# Amiga_Parallel_SD_Rev_2.net
KiCad netlist of a schematic drawn in EAGLE
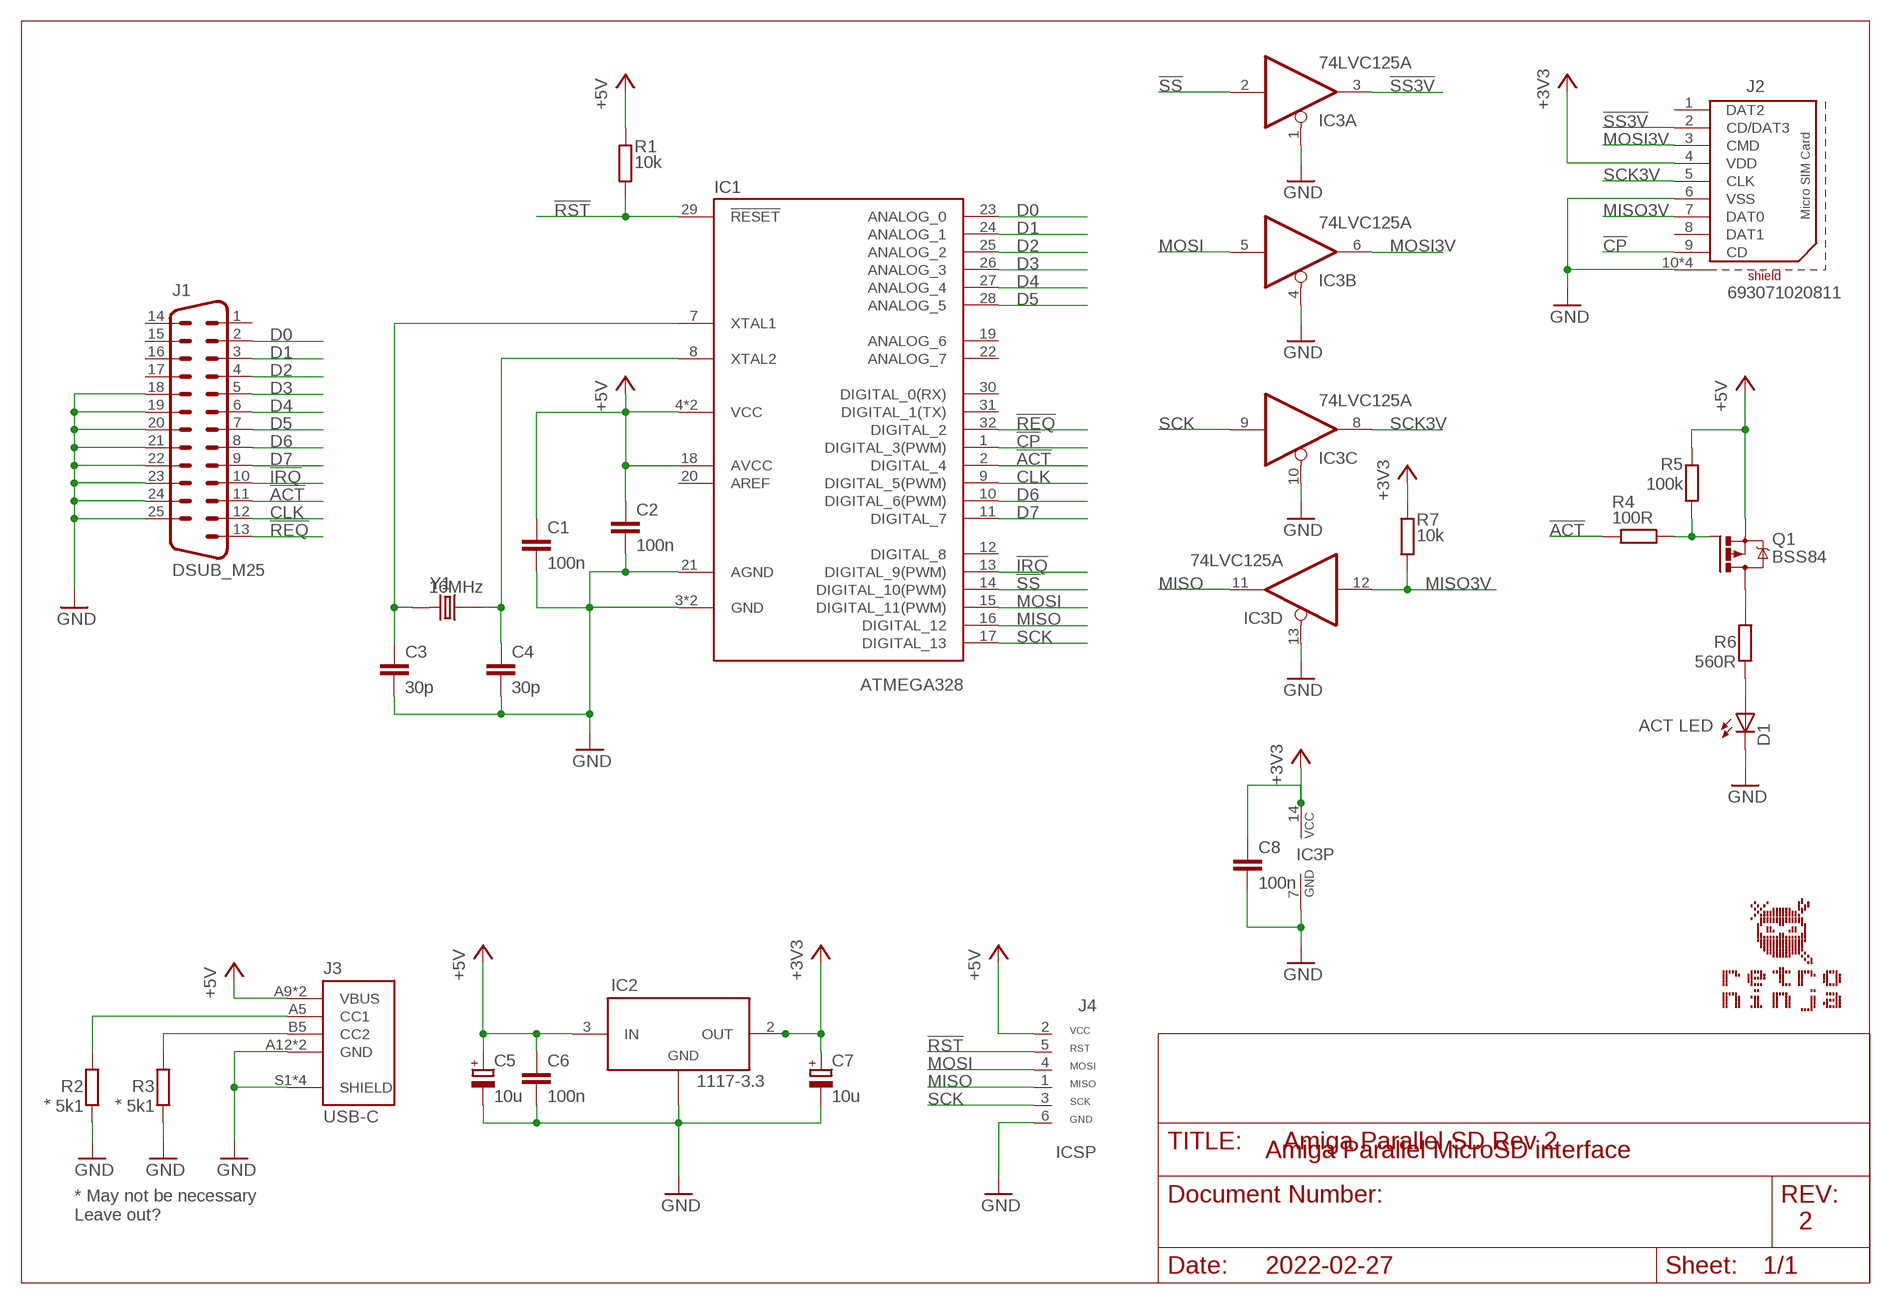
[diagram p0: schematic, sheet 1]

(export (version "E")
  (design (tool "Eeschema 10.0.6"))
  (components
    (comp (ref "C1")
      (value "100n")
      (footprint "eagle-import:C0805")
      (libsource (lib "eagle-import") (part "C-EUC0805"))
    )
    (comp (ref "C2")
      (value "100n")
      (footprint "eagle-import:C0805")
      (libsource (lib "eagle-import") (part "C-EUC0805"))
    )
    (comp (ref "C3")
      (value "30p")
      (footprint "eagle-import:C0805")
      (libsource (lib "eagle-import") (part "C-EUC0805"))
    )
    (comp (ref "C4")
      (value "30p")
      (footprint "eagle-import:C0805")
      (libsource (lib "eagle-import") (part "C-EUC0805"))
    )
    (comp (ref "C5")
      (value "10u")
      (footprint "eagle-import:TANTALUM_0805")
      (libsource (lib "eagle-import") (part "CAPACITOR_POL_TANT_0805"))
    )
    (comp (ref "C6")
      (value "100n")
      (footprint "eagle-import:C0805")
      (libsource (lib "eagle-import") (part "C-EUC0805"))
    )
    (comp (ref "C7")
      (value "10u")
      (footprint "eagle-import:TANTALUM_0805")
      (libsource (lib "eagle-import") (part "CAPACITOR_POL_TANT_0805"))
    )
    (comp (ref "C8")
      (value "100n")
      (footprint "eagle-import:C0805")
      (libsource (lib "eagle-import") (part "C-EUC0805"))
    )
    (comp (ref "D1")
      (value "LED_3MM_GREEN")
      (footprint "eagle-import:LED3MM_GREEN")
      (libsource (lib "eagle-import") (part "LED_3MM_GREEN"))
    )
    (comp (ref "IC1")
      (value "ATMEGA328")
      (footprint "eagle-import:TQFP-32")
      (libsource (lib "eagle-import") (part "ARDUINO_168_328_TQFP"))
    )
    (comp (ref "IC2")
      (value "1117-3.3")
      (footprint "eagle-import:SOT-223")
      (fields
        (field (name "DIGIKEY_PART_NUMBER") "NCP1117ST33T3GOSTR-ND")
        (field (name "MANUFACTURER") "ON Semiconductor")
        (field (name "MPN") "NCP1117ST33T3G")
        (field (name "CREATED_BY") "PCBLayout.com")
      )
      (libsource (lib "eagle-import") (part "NCP1117ST33T3G"))
    )
    (comp (ref "IC3")
      (value "74LVC125A")
      (footprint "eagle-import:SO14")
      (libsource (lib "eagle-import") (part "74125DHC"))
    )
    (comp (ref "J1")
      (value "DSUB_M25")
      (footprint "eagle-import:DSUB_M25D")
      (libsource (lib "eagle-import") (part "DSUB_M25"))
    )
    (comp (ref "J2")
      (value "693071020811")
      (footprint "eagle-import:693071020811")
      (libsource (lib "eagle-import") (part "693071020811"))
    )
    (comp (ref "J3")
      (value "USB-C")
      (footprint "eagle-import:MOLEX_2171750001")
      (fields (field (name "MANUFACTURER") "Molex"))
      (libsource (lib "eagle-import") (part "USB-C"))
    )
    (comp (ref "J4")
      (value "ICSP")
      (footprint "eagle-import:HEADER_2X3_ALT")
      (libsource (lib "eagle-import") (part "ICSP_CONNECTOR_6_ALT"))
    )
    (comp (ref "Q1")
      (value "BSS84")
      (footprint "eagle-import:SOT23")
      (libsource (lib "eagle-import") (part "PMOSFETSOT23_"))
    )
    (comp (ref "R1")
      (value "10k")
      (footprint "eagle-import:R0805")
      (libsource (lib "eagle-import") (part "R-EU_R0805"))
    )
    (comp (ref "R2")
      (value "5k1")
      (footprint "eagle-import:R0805")
      (libsource (lib "eagle-import") (part "R-EU_R0805"))
    )
    (comp (ref "R3")
      (value "5k1")
      (footprint "eagle-import:R0805")
      (libsource (lib "eagle-import") (part "R-EU_R0805"))
    )
    (comp (ref "R4")
      (value "100R")
      (footprint "eagle-import:R0805")
      (libsource (lib "eagle-import") (part "R-EU_R0805"))
    )
    (comp (ref "R5")
      (value "100k")
      (footprint "eagle-import:R0805")
      (libsource (lib "eagle-import") (part "R-EU_R0805"))
    )
    (comp (ref "R6")
      (value "560R")
      (footprint "eagle-import:R0805")
      (libsource (lib "eagle-import") (part "R-EU_R0805"))
    )
    (comp (ref "R7")
      (value "10k")
      (footprint "eagle-import:R0805")
      (libsource (lib "eagle-import") (part "R-EU_R0805"))
    )
    (comp (ref "Y1")
      (value "16MHz")
      (footprint "eagle-import:CRYSTAL_SMD-2_7X4X2.3")
      (libsource (lib "eagle-import") (part "CRYSTAL"))
    )
  )
  (nets
    (net (code "1") (name "+3V3") (class "Default")
      (node (ref "C7") (pin "+") (pinfunction "+_+") (pintype "passive"))
      (node (ref "C8") (pin "1") (pinfunction "1_1") (pintype "passive"))
      (node (ref "IC2") (pin "2") (pinfunction "OUT_2") (pintype "output"))
      (node (ref "IC2") (pin "4") (pinfunction "4_4") (pintype "passive"))
      (node (ref "IC3") (pin "14") (pinfunction "VCC_14") (pintype "power_in"))
      (node (ref "J2") (pin "4") (pinfunction "VDD_4") (pintype "bidirectional"))
      (node (ref "R7") (pin "1") (pinfunction "1_1") (pintype "passive"))
    )
    (net (code "2") (name "+5V") (class "Default")
      (node (ref "C1") (pin "1") (pinfunction "1_1") (pintype "passive"))
      (node (ref "C2") (pin "1") (pinfunction "1_1") (pintype "passive"))
      (node (ref "C5") (pin "+") (pinfunction "+_+") (pintype "passive"))
      (node (ref "C6") (pin "1") (pinfunction "1_1") (pintype "passive"))
      (node (ref "IC1") (pin "18") (pinfunction "AVCC_18") (pintype "passive"))
      (node (ref "IC1") (pin "4") (pinfunction "VCC_4") (pintype "passive"))
      (node (ref "IC1") (pin "6") (pinfunction "VCC_6") (pintype "passive"))
      (node (ref "IC2") (pin "3") (pinfunction "IN_3") (pintype "input"))
      (node (ref "J3") (pin "A9") (pinfunction "VBUS_A9") (pintype "power_in"))
      (node (ref "J3") (pin "B9") (pinfunction "VBUS_B9") (pintype "power_in"))
      (node (ref "J4") (pin "2") (pinfunction "VCC_2") (pintype "power_in"))
      (node (ref "Q1") (pin "2") (pinfunction "S_2") (pintype "passive"))
      (node (ref "R1") (pin "1") (pinfunction "1_1") (pintype "passive"))
      (node (ref "R5") (pin "2") (pinfunction "2_2") (pintype "passive"))
    )
    (net (code "3") (name "/CLK") (class "Default")
      (node (ref "IC1") (pin "9") (pinfunction "DIGITAL_5(PWM)_9") (pintype "bidirectional"))
      (node (ref "J1") (pin "12") (pinfunction "12_12") (pintype "passive"))
    )
    (net (code "4") (name "/D0") (class "Default")
      (node (ref "IC1") (pin "23") (pinfunction "ANALOG_0_23") (pintype "bidirectional"))
      (node (ref "J1") (pin "2") (pinfunction "2_2") (pintype "passive"))
    )
    (net (code "5") (name "/D1") (class "Default")
      (node (ref "IC1") (pin "24") (pinfunction "ANALOG_1_24") (pintype "bidirectional"))
      (node (ref "J1") (pin "3") (pinfunction "3_3") (pintype "passive"))
    )
    (net (code "6") (name "/D2") (class "Default")
      (node (ref "IC1") (pin "25") (pinfunction "ANALOG_2_25") (pintype "bidirectional"))
      (node (ref "J1") (pin "4") (pinfunction "4_4") (pintype "passive"))
    )
    (net (code "7") (name "/D3") (class "Default")
      (node (ref "IC1") (pin "26") (pinfunction "ANALOG_3_26") (pintype "bidirectional"))
      (node (ref "J1") (pin "5") (pinfunction "5_5") (pintype "passive"))
    )
    (net (code "8") (name "/D4") (class "Default")
      (node (ref "IC1") (pin "27") (pinfunction "ANALOG_4_27") (pintype "bidirectional"))
      (node (ref "J1") (pin "6") (pinfunction "6_6") (pintype "passive"))
    )
    (net (code "9") (name "/D5") (class "Default")
      (node (ref "IC1") (pin "28") (pinfunction "ANALOG_5_28") (pintype "bidirectional"))
      (node (ref "J1") (pin "7") (pinfunction "7_7") (pintype "passive"))
    )
    (net (code "10") (name "/D6") (class "Default")
      (node (ref "IC1") (pin "10") (pinfunction "DIGITAL_6(PWM)_10") (pintype "bidirectional"))
      (node (ref "J1") (pin "8") (pinfunction "8_8") (pintype "passive"))
    )
    (net (code "11") (name "/D7") (class "Default")
      (node (ref "IC1") (pin "11") (pinfunction "DIGITAL_7_11") (pintype "bidirectional"))
      (node (ref "J1") (pin "9") (pinfunction "9_9") (pintype "passive"))
    )
    (net (code "12") (name "/MISO") (class "Default")
      (node (ref "IC1") (pin "16") (pinfunction "DIGITAL_12_16") (pintype "bidirectional"))
      (node (ref "IC3") (pin "11") (pinfunction "O_11") (pintype "tri_state"))
      (node (ref "J4") (pin "1") (pinfunction "MISO_1") (pintype "output"))
    )
    (net (code "13") (name "/MISO3V") (class "Default")
      (node (ref "IC3") (pin "12") (pinfunction "I_12") (pintype "input"))
      (node (ref "J2") (pin "7") (pinfunction "DAT0_7") (pintype "bidirectional"))
      (node (ref "R7") (pin "2") (pinfunction "2_2") (pintype "passive"))
    )
    (net (code "14") (name "/MOSI") (class "Default")
      (node (ref "IC1") (pin "15") (pinfunction "DIGITAL_11(PWM)_15") (pintype "bidirectional"))
      (node (ref "IC3") (pin "5") (pinfunction "I_5") (pintype "input"))
      (node (ref "J4") (pin "4") (pinfunction "MOSI_4") (pintype "input"))
    )
    (net (code "15") (name "/MOSI3V") (class "Default")
      (node (ref "IC3") (pin "6") (pinfunction "O_6") (pintype "tri_state"))
      (node (ref "J2") (pin "3") (pinfunction "CMD_3") (pintype "bidirectional"))
    )
    (net (code "16") (name "/SCK") (class "Default")
      (node (ref "IC1") (pin "17") (pinfunction "DIGITAL_13_17") (pintype "bidirectional"))
      (node (ref "IC3") (pin "9") (pinfunction "I_9") (pintype "input"))
      (node (ref "J4") (pin "3") (pinfunction "SCK_3") (pintype "input"))
    )
    (net (code "17") (name "/SCK3V") (class "Default")
      (node (ref "IC3") (pin "8") (pinfunction "O_8") (pintype "tri_state"))
      (node (ref "J2") (pin "5") (pinfunction "CLK_5") (pintype "bidirectional"))
    )
    (net (code "18") (name "/~{ACT}") (class "Default")
      (node (ref "IC1") (pin "2") (pinfunction "DIGITAL_4_2") (pintype "bidirectional"))
      (node (ref "J1") (pin "11") (pinfunction "11_11") (pintype "passive"))
      (node (ref "R4") (pin "2") (pinfunction "2_2") (pintype "passive"))
    )
    (net (code "19") (name "/~{CP}") (class "Default")
      (node (ref "IC1") (pin "1") (pinfunction "DIGITAL_3(PWM)_1") (pintype "bidirectional"))
      (node (ref "J2") (pin "9") (pinfunction "CD_9") (pintype "bidirectional"))
    )
    (net (code "20") (name "/~{IRQ}") (class "Default")
      (node (ref "IC1") (pin "13") (pinfunction "DIGITAL_9(PWM)_13") (pintype "bidirectional"))
      (node (ref "J1") (pin "10") (pinfunction "10_10") (pintype "passive"))
    )
    (net (code "21") (name "/~{REQ}") (class "Default")
      (node (ref "IC1") (pin "32") (pinfunction "DIGITAL_2_32") (pintype "bidirectional"))
      (node (ref "J1") (pin "13") (pinfunction "13_13") (pintype "passive"))
    )
    (net (code "22") (name "/~{RST}") (class "Default")
      (node (ref "IC1") (pin "29") (pinfunction "~{RESET}_29") (pintype "bidirectional"))
      (node (ref "J4") (pin "5") (pinfunction "RST_5") (pintype "input"))
      (node (ref "R1") (pin "2") (pinfunction "2_2") (pintype "passive"))
    )
    (net (code "23") (name "/~{SS3V}") (class "Default")
      (node (ref "IC3") (pin "3") (pinfunction "O_3") (pintype "tri_state"))
      (node (ref "J2") (pin "2") (pinfunction "CD/DAT3_2") (pintype "bidirectional"))
    )
    (net (code "24") (name "/~{SS}") (class "Default")
      (node (ref "IC1") (pin "14") (pinfunction "DIGITAL_10(PWM)_14") (pintype "bidirectional"))
      (node (ref "IC3") (pin "2") (pinfunction "I_2") (pintype "input"))
    )
    (net (code "25") (name "GND") (class "Default")
      (node (ref "C1") (pin "2") (pinfunction "2_2") (pintype "passive"))
      (node (ref "C2") (pin "2") (pinfunction "2_2") (pintype "passive"))
      (node (ref "C3") (pin "2") (pinfunction "2_2") (pintype "passive"))
      (node (ref "C4") (pin "2") (pinfunction "2_2") (pintype "passive"))
      (node (ref "C5") (pin "-") (pinfunction "-_-") (pintype "passive"))
      (node (ref "C6") (pin "2") (pinfunction "2_2") (pintype "passive"))
      (node (ref "C7") (pin "-") (pinfunction "-_-") (pintype "passive"))
      (node (ref "C8") (pin "2") (pinfunction "2_2") (pintype "passive"))
      (node (ref "D1") (pin "K") (pinfunction "C_K") (pintype "passive"))
      (node (ref "IC1") (pin "21") (pinfunction "AGND_21") (pintype "passive"))
      (node (ref "IC1") (pin "3") (pinfunction "GND_3") (pintype "passive"))
      (node (ref "IC1") (pin "5") (pinfunction "GND_5") (pintype "passive"))
      (node (ref "IC2") (pin "1") (pinfunction "ADJ/GND_1") (pintype "power_in"))
      (node (ref "IC3") (pin "1") (pinfunction "OE_1") (pintype "input"))
      (node (ref "IC3") (pin "10") (pinfunction "OE_10") (pintype "input"))
      (node (ref "IC3") (pin "13") (pinfunction "OE_13") (pintype "input"))
      (node (ref "IC3") (pin "4") (pinfunction "OE_4") (pintype "input"))
      (node (ref "IC3") (pin "7") (pinfunction "GND_7") (pintype "power_in"))
      (node (ref "J1") (pin "18") (pinfunction "18_18") (pintype "passive"))
      (node (ref "J1") (pin "19") (pinfunction "19_19") (pintype "passive"))
      (node (ref "J1") (pin "20") (pinfunction "20_20") (pintype "passive"))
      (node (ref "J1") (pin "21") (pinfunction "21_21") (pintype "passive"))
      (node (ref "J1") (pin "22") (pinfunction "22_22") (pintype "passive"))
      (node (ref "J1") (pin "23") (pinfunction "23_23") (pintype "passive"))
      (node (ref "J1") (pin "24") (pinfunction "24_24") (pintype "passive"))
      (node (ref "J1") (pin "25") (pinfunction "25_25") (pintype "passive"))
      (node (ref "J2") (pin "10") (pinfunction "SHIELD_10") (pintype "bidirectional"))
      (node (ref "J2") (pin "11") (pinfunction "SHIELD_11") (pintype "bidirectional"))
      (node (ref "J2") (pin "12") (pinfunction "SHIELD_12") (pintype "bidirectional"))
      (node (ref "J2") (pin "13") (pinfunction "SHIELD_13") (pintype "bidirectional"))
      (node (ref "J2") (pin "6") (pinfunction "VSS_6") (pintype "bidirectional"))
      (node (ref "J3") (pin "A12") (pinfunction "GND_A12") (pintype "power_in"))
      (node (ref "J3") (pin "B12") (pinfunction "GND_B12") (pintype "power_in"))
      (node (ref "J3") (pin "S1") (pinfunction "SHIELD_S1") (pintype "passive"))
      (node (ref "J3") (pin "S2") (pinfunction "SHIELD_S2") (pintype "passive"))
      (node (ref "J3") (pin "S3") (pinfunction "SHIELD_S3") (pintype "passive"))
      (node (ref "J3") (pin "S4") (pinfunction "SHIELD_S4") (pintype "passive"))
      (node (ref "J4") (pin "6") (pinfunction "GND_6") (pintype "power_in"))
      (node (ref "R2") (pin "1") (pinfunction "1_1") (pintype "passive"))
      (node (ref "R3") (pin "1") (pinfunction "1_1") (pintype "passive"))
    )
    (net (code "26") (name "Net-(D1-PadA)") (class "Default")
      (node (ref "D1") (pin "A") (pinfunction "A_A") (pintype "passive"))
      (node (ref "R6") (pin "1") (pinfunction "1_1") (pintype "passive"))
    )
    (net (code "27") (name "Net-(IC1-XTAL1)") (class "Default")
      (node (ref "C3") (pin "1") (pinfunction "1_1") (pintype "passive"))
      (node (ref "IC1") (pin "7") (pinfunction "XTAL1_7") (pintype "bidirectional"))
      (node (ref "Y1") (pin "2") (pinfunction "2_2") (pintype "passive"))
    )
    (net (code "28") (name "Net-(IC1-XTAL2)") (class "Default")
      (node (ref "C4") (pin "1") (pinfunction "1_1") (pintype "passive"))
      (node (ref "IC1") (pin "8") (pinfunction "XTAL2_8") (pintype "bidirectional"))
      (node (ref "Y1") (pin "1") (pinfunction "1_1") (pintype "passive"))
    )
    (net (code "29") (name "Net-(J3-CC1)") (class "Default")
      (node (ref "J3") (pin "A5") (pinfunction "CC1_A5") (pintype "bidirectional"))
      (node (ref "R2") (pin "2") (pinfunction "2_2") (pintype "passive"))
    )
    (net (code "30") (name "Net-(J3-CC2)") (class "Default")
      (node (ref "J3") (pin "B5") (pinfunction "CC2_B5") (pintype "bidirectional"))
      (node (ref "R3") (pin "2") (pinfunction "2_2") (pintype "passive"))
    )
    (net (code "31") (name "Net-(Q1-D)") (class "Default")
      (node (ref "Q1") (pin "3") (pinfunction "D_3") (pintype "passive"))
      (node (ref "R6") (pin "2") (pinfunction "2_2") (pintype "passive"))
    )
    (net (code "32") (name "Net-(Q1-G)") (class "Default")
      (node (ref "Q1") (pin "1") (pinfunction "G_1") (pintype "passive"))
      (node (ref "R4") (pin "1") (pinfunction "1_1") (pintype "passive"))
      (node (ref "R5") (pin "1") (pinfunction "1_1") (pintype "passive"))
    )
    (net (code "33") (name "unconnected-(IC1-ANALOG_6-Pad19)") (class "Default")
      (node (ref "IC1") (pin "19") (pinfunction "ANALOG_6_19") (pintype "bidirectional"))
    )
    (net (code "34") (name "unconnected-(IC1-ANALOG_7-Pad22)") (class "Default")
      (node (ref "IC1") (pin "22") (pinfunction "ANALOG_7_22") (pintype "bidirectional"))
    )
    (net (code "35") (name "unconnected-(IC1-AREF-Pad20)") (class "Default")
      (node (ref "IC1") (pin "20") (pinfunction "AREF_20") (pintype "passive"))
    )
    (net (code "36") (name "unconnected-(IC1-DIGITAL_0(RX)-Pad30)") (class "Default")
      (node (ref "IC1") (pin "30") (pinfunction "DIGITAL_0(RX)_30") (pintype "bidirectional"))
    )
    (net (code "37") (name "unconnected-(IC1-DIGITAL_1(TX)-Pad31)") (class "Default")
      (node (ref "IC1") (pin "31") (pinfunction "DIGITAL_1(TX)_31") (pintype "bidirectional"))
    )
    (net (code "38") (name "unconnected-(IC1-DIGITAL_8-Pad12)") (class "Default")
      (node (ref "IC1") (pin "12") (pinfunction "DIGITAL_8_12") (pintype "bidirectional"))
    )
    (net (code "39") (name "unconnected-(J1-Pad1)") (class "Default")
      (node (ref "J1") (pin "1") (pinfunction "1_1") (pintype "passive"))
    )
    (net (code "40") (name "unconnected-(J1-Pad14)") (class "Default")
      (node (ref "J1") (pin "14") (pinfunction "14_14") (pintype "passive"))
    )
    (net (code "41") (name "unconnected-(J1-Pad15)") (class "Default")
      (node (ref "J1") (pin "15") (pinfunction "15_15") (pintype "passive"))
    )
    (net (code "42") (name "unconnected-(J1-Pad16)") (class "Default")
      (node (ref "J1") (pin "16") (pinfunction "16_16") (pintype "passive"))
    )
    (net (code "43") (name "unconnected-(J1-Pad17)") (class "Default")
      (node (ref "J1") (pin "17") (pinfunction "17_17") (pintype "passive"))
    )
    (net (code "44") (name "unconnected-(J2-DAT1-Pad8)") (class "Default")
      (node (ref "J2") (pin "8") (pinfunction "DAT1_8") (pintype "bidirectional"))
    )
    (net (code "45") (name "unconnected-(J2-DAT2-Pad1)") (class "Default")
      (node (ref "J2") (pin "1") (pinfunction "DAT2_1") (pintype "bidirectional"))
    )
  )
)
